# sensornode.net
KiCad netlist of a schematic drawn in EAGLE
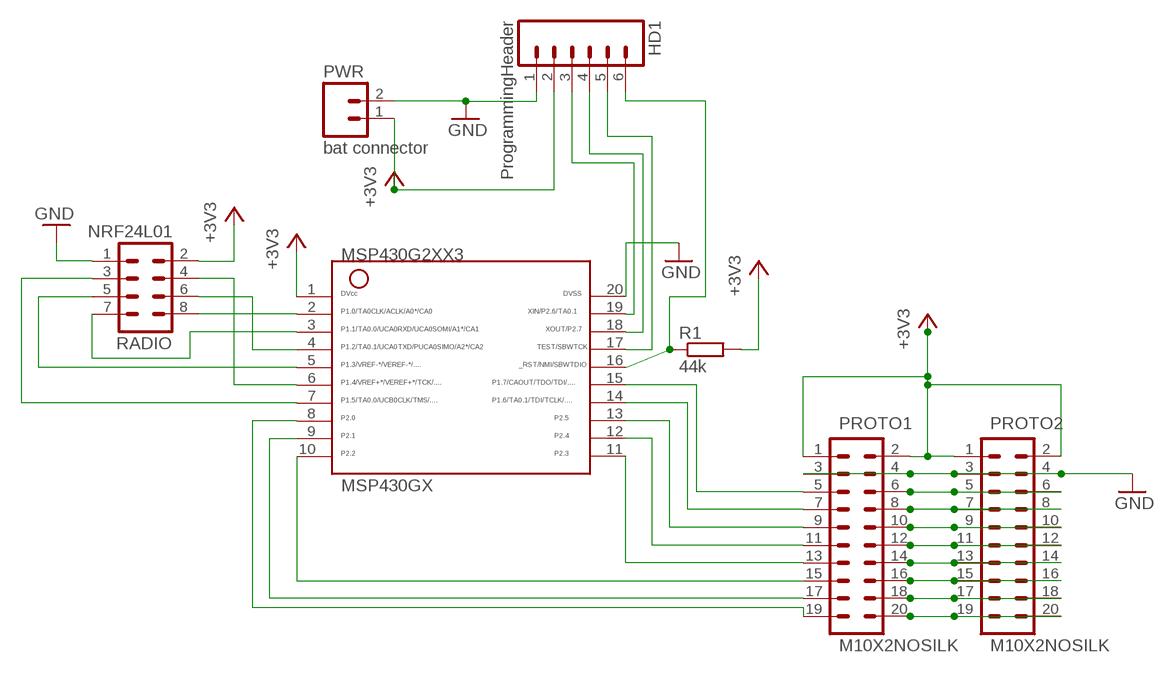
[diagram p0: schematic, sheet 1]

(export (version "E")
  (design (tool "Eeschema 10.0.6"))
  (components
    (comp (ref "HD1")
      (value "ProgrammingHeader")
      (footprint "eagle-import:1X06")
      (libsource (lib "eagle-import") (part "M06SIP"))
    )
    (comp (ref "MSP430GX")
      (value "G2XX3---N20")
      (footprint "eagle-import:N20")
      (libsource (lib "eagle-import") (part "G2XX3---N20"))
    )
    (comp (ref "PROTO1")
      (value "M10X2NOSILK")
      (footprint "eagle-import:2X10_NOSILK")
      (libsource (lib "eagle-import") (part "M10X2NOSILK"))
    )
    (comp (ref "PROTO2")
      (value "M10X2NOSILK")
      (footprint "eagle-import:2X10_NOSILK")
      (libsource (lib "eagle-import") (part "M10X2NOSILK"))
    )
    (comp (ref "PWR")
      (value "bat connector")
      (footprint "eagle-import:SCREWTERMINAL-5MM-2")
      (libsource (lib "eagle-import") (part "M025MM"))
    )
    (comp (ref "R1")
      (value "44k")
      (footprint "eagle-import:0207_10")
      (libsource (lib "eagle-import") (part "R-EU_0207/10"))
    )
    (comp (ref "RADIO")
      (value "NRF24L01")
      (footprint "eagle-import:MA04-2")
      (libsource (lib "eagle-import") (part "MA04-2"))
    )
  )
  (nets
    (net (code "1") (name "+3V3") (class "Default")
      (node (ref "HD1") (pin "2") (pinfunction "2_2") (pintype "passive"))
      (node (ref "MSP430GX") (pin "1") (pinfunction "1_1") (pintype "bidirectional"))
      (node (ref "PROTO1") (pin "1") (pinfunction "1_1") (pintype "passive"))
      (node (ref "PROTO1") (pin "2") (pinfunction "2_2") (pintype "passive"))
      (node (ref "PROTO2") (pin "1") (pinfunction "1_1") (pintype "passive"))
      (node (ref "PROTO2") (pin "2") (pinfunction "2_2") (pintype "passive"))
      (node (ref "PWR") (pin "1") (pinfunction "1_1") (pintype "passive"))
      (node (ref "R1") (pin "2") (pinfunction "2_2") (pintype "passive"))
      (node (ref "RADIO") (pin "2") (pinfunction "2_2") (pintype "passive"))
    )
    (net (code "2") (name "GND") (class "Default")
      (node (ref "HD1") (pin "1") (pinfunction "1_1") (pintype "passive"))
      (node (ref "MSP430GX") (pin "20") (pinfunction "20_20") (pintype "bidirectional"))
      (node (ref "PROTO1") (pin "3") (pinfunction "3_3") (pintype "passive"))
      (node (ref "PROTO1") (pin "4") (pinfunction "4_4") (pintype "passive"))
      (node (ref "PROTO2") (pin "3") (pinfunction "3_3") (pintype "passive"))
      (node (ref "PROTO2") (pin "4") (pinfunction "4_4") (pintype "passive"))
      (node (ref "PWR") (pin "2") (pinfunction "2_2") (pintype "passive"))
      (node (ref "RADIO") (pin "1") (pinfunction "1_1") (pintype "passive"))
    )
    (net (code "3") (name "Net-(HD1-Pad3)") (class "Default")
      (node (ref "HD1") (pin "3") (pinfunction "3_3") (pintype "passive"))
      (node (ref "MSP430GX") (pin "19") (pinfunction "19_19") (pintype "bidirectional"))
    )
    (net (code "4") (name "Net-(HD1-Pad4)") (class "Default")
      (node (ref "HD1") (pin "4") (pinfunction "4_4") (pintype "passive"))
      (node (ref "MSP430GX") (pin "18") (pinfunction "18_18") (pintype "bidirectional"))
    )
    (net (code "5") (name "Net-(HD1-Pad5)") (class "Default")
      (node (ref "HD1") (pin "5") (pinfunction "5_5") (pintype "passive"))
      (node (ref "MSP430GX") (pin "17") (pinfunction "17_17") (pintype "bidirectional"))
    )
    (net (code "6") (name "Net-(HD1-Pad6)") (class "Default")
      (node (ref "HD1") (pin "6") (pinfunction "6_6") (pintype "passive"))
      (node (ref "MSP430GX") (pin "16") (pinfunction "16_16") (pintype "bidirectional"))
      (node (ref "R1") (pin "1") (pinfunction "1_1") (pintype "passive"))
    )
    (net (code "7") (name "Net-(MSP430GX-Pad2)") (class "Default")
      (node (ref "MSP430GX") (pin "2") (pinfunction "2_2") (pintype "bidirectional"))
      (node (ref "RADIO") (pin "8") (pinfunction "8_8") (pintype "passive"))
    )
    (net (code "8") (name "Net-(MSP430GX-Pad3)") (class "Default")
      (node (ref "MSP430GX") (pin "3") (pinfunction "3_3") (pintype "bidirectional"))
      (node (ref "RADIO") (pin "7") (pinfunction "7_7") (pintype "passive"))
    )
    (net (code "9") (name "Net-(MSP430GX-Pad4)") (class "Default")
      (node (ref "MSP430GX") (pin "4") (pinfunction "4_4") (pintype "bidirectional"))
      (node (ref "RADIO") (pin "6") (pinfunction "6_6") (pintype "passive"))
    )
    (net (code "10") (name "Net-(MSP430GX-Pad5)") (class "Default")
      (node (ref "MSP430GX") (pin "5") (pinfunction "5_5") (pintype "bidirectional"))
      (node (ref "RADIO") (pin "5") (pinfunction "5_5") (pintype "passive"))
    )
    (net (code "11") (name "Net-(MSP430GX-Pad6)") (class "Default")
      (node (ref "MSP430GX") (pin "6") (pinfunction "6_6") (pintype "bidirectional"))
      (node (ref "RADIO") (pin "4") (pinfunction "4_4") (pintype "passive"))
    )
    (net (code "12") (name "Net-(MSP430GX-Pad7)") (class "Default")
      (node (ref "MSP430GX") (pin "7") (pinfunction "7_7") (pintype "bidirectional"))
      (node (ref "RADIO") (pin "3") (pinfunction "3_3") (pintype "passive"))
    )
    (net (code "13") (name "Net-(MSP430GX-Pad8)") (class "Default")
      (node (ref "MSP430GX") (pin "8") (pinfunction "8_8") (pintype "bidirectional"))
      (node (ref "PROTO1") (pin "19") (pinfunction "19_19") (pintype "passive"))
    )
    (net (code "14") (name "Net-(MSP430GX-Pad9)") (class "Default")
      (node (ref "MSP430GX") (pin "9") (pinfunction "9_9") (pintype "bidirectional"))
      (node (ref "PROTO1") (pin "17") (pinfunction "17_17") (pintype "passive"))
    )
    (net (code "15") (name "Net-(MSP430GX-Pad10)") (class "Default")
      (node (ref "MSP430GX") (pin "10") (pinfunction "10_10") (pintype "bidirectional"))
      (node (ref "PROTO1") (pin "15") (pinfunction "15_15") (pintype "passive"))
    )
    (net (code "16") (name "Net-(MSP430GX-Pad11)") (class "Default")
      (node (ref "MSP430GX") (pin "11") (pinfunction "11_11") (pintype "bidirectional"))
      (node (ref "PROTO1") (pin "13") (pinfunction "13_13") (pintype "passive"))
    )
    (net (code "17") (name "Net-(MSP430GX-Pad12)") (class "Default")
      (node (ref "MSP430GX") (pin "12") (pinfunction "12_12") (pintype "bidirectional"))
      (node (ref "PROTO1") (pin "11") (pinfunction "11_11") (pintype "passive"))
    )
    (net (code "18") (name "Net-(MSP430GX-Pad13)") (class "Default")
      (node (ref "MSP430GX") (pin "13") (pinfunction "13_13") (pintype "bidirectional"))
      (node (ref "PROTO1") (pin "9") (pinfunction "9_9") (pintype "passive"))
    )
    (net (code "19") (name "Net-(MSP430GX-Pad14)") (class "Default")
      (node (ref "MSP430GX") (pin "14") (pinfunction "14_14") (pintype "bidirectional"))
      (node (ref "PROTO1") (pin "7") (pinfunction "7_7") (pintype "passive"))
    )
    (net (code "20") (name "Net-(MSP430GX-Pad15)") (class "Default")
      (node (ref "MSP430GX") (pin "15") (pinfunction "15_15") (pintype "bidirectional"))
      (node (ref "PROTO1") (pin "5") (pinfunction "5_5") (pintype "passive"))
    )
    (net (code "21") (name "Net-(PROTO1-Pad6)") (class "Default")
      (node (ref "PROTO1") (pin "6") (pinfunction "6_6") (pintype "passive"))
      (node (ref "PROTO2") (pin "5") (pinfunction "5_5") (pintype "passive"))
      (node (ref "PROTO2") (pin "6") (pinfunction "6_6") (pintype "passive"))
    )
    (net (code "22") (name "Net-(PROTO1-Pad8)") (class "Default")
      (node (ref "PROTO1") (pin "8") (pinfunction "8_8") (pintype "passive"))
      (node (ref "PROTO2") (pin "7") (pinfunction "7_7") (pintype "passive"))
      (node (ref "PROTO2") (pin "8") (pinfunction "8_8") (pintype "passive"))
    )
    (net (code "23") (name "Net-(PROTO1-Pad10)") (class "Default")
      (node (ref "PROTO1") (pin "10") (pinfunction "10_10") (pintype "passive"))
      (node (ref "PROTO2") (pin "10") (pinfunction "10_10") (pintype "passive"))
      (node (ref "PROTO2") (pin "9") (pinfunction "9_9") (pintype "passive"))
    )
    (net (code "24") (name "Net-(PROTO1-Pad12)") (class "Default")
      (node (ref "PROTO1") (pin "12") (pinfunction "12_12") (pintype "passive"))
      (node (ref "PROTO2") (pin "11") (pinfunction "11_11") (pintype "passive"))
      (node (ref "PROTO2") (pin "12") (pinfunction "12_12") (pintype "passive"))
    )
    (net (code "25") (name "Net-(PROTO1-Pad14)") (class "Default")
      (node (ref "PROTO1") (pin "14") (pinfunction "14_14") (pintype "passive"))
      (node (ref "PROTO2") (pin "13") (pinfunction "13_13") (pintype "passive"))
      (node (ref "PROTO2") (pin "14") (pinfunction "14_14") (pintype "passive"))
    )
    (net (code "26") (name "Net-(PROTO1-Pad16)") (class "Default")
      (node (ref "PROTO1") (pin "16") (pinfunction "16_16") (pintype "passive"))
      (node (ref "PROTO2") (pin "15") (pinfunction "15_15") (pintype "passive"))
      (node (ref "PROTO2") (pin "16") (pinfunction "16_16") (pintype "passive"))
    )
    (net (code "27") (name "Net-(PROTO1-Pad18)") (class "Default")
      (node (ref "PROTO1") (pin "18") (pinfunction "18_18") (pintype "passive"))
      (node (ref "PROTO2") (pin "17") (pinfunction "17_17") (pintype "passive"))
      (node (ref "PROTO2") (pin "18") (pinfunction "18_18") (pintype "passive"))
    )
    (net (code "28") (name "Net-(PROTO1-Pad20)") (class "Default")
      (node (ref "PROTO1") (pin "20") (pinfunction "20_20") (pintype "passive"))
      (node (ref "PROTO2") (pin "19") (pinfunction "19_19") (pintype "passive"))
      (node (ref "PROTO2") (pin "20") (pinfunction "20_20") (pintype "passive"))
    )
  )
)
